# harvester.net
KiCad netlist of a schematic drawn in Altium Designer
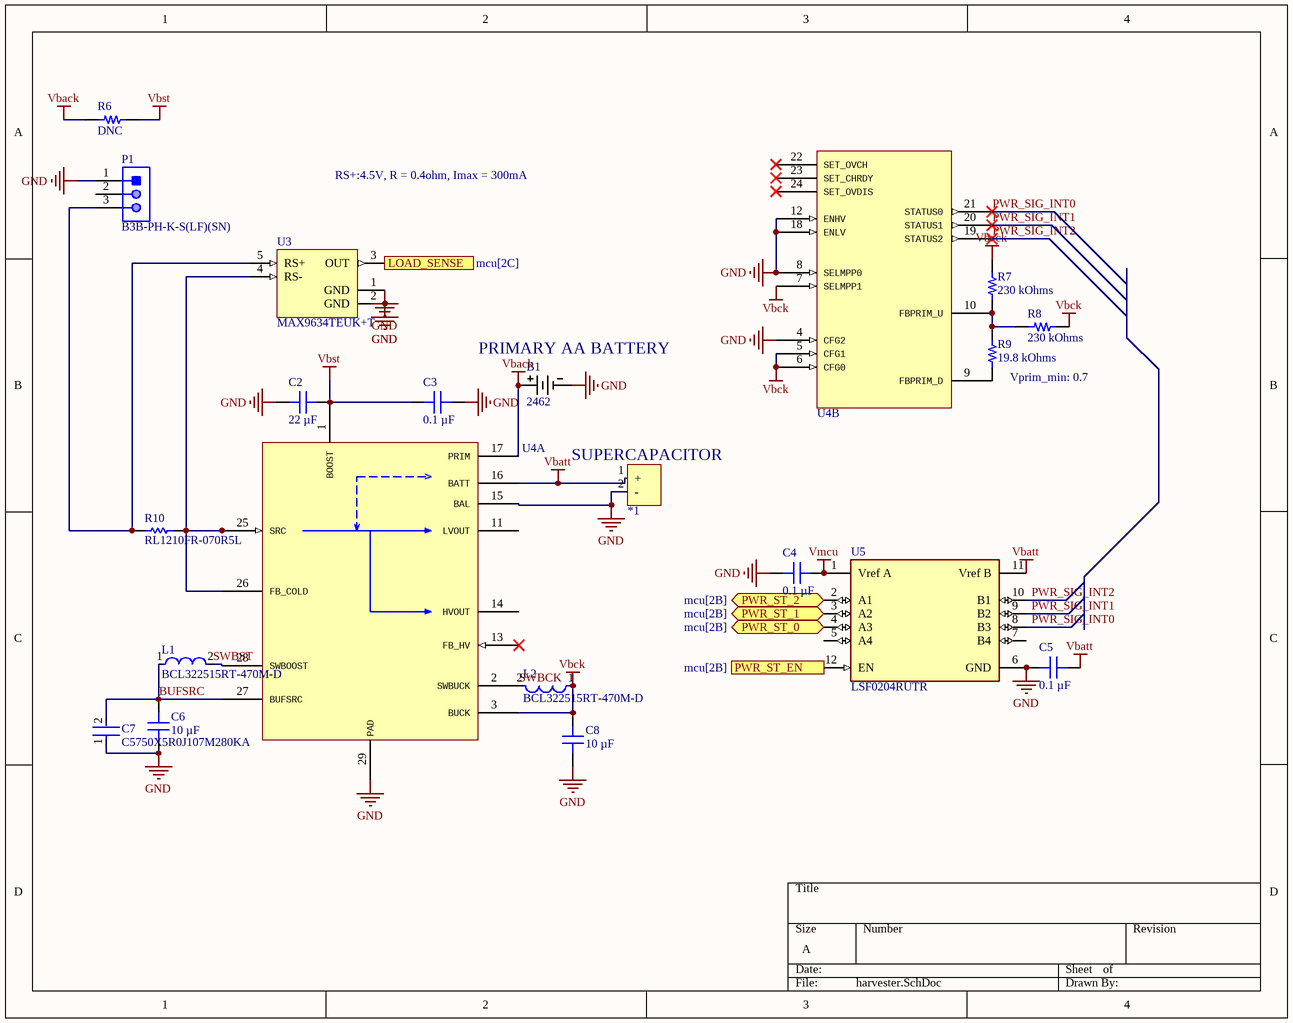
[diagram p0: harvester.SchDoc]

(export (version "E")
  (design (tool "Eeschema 10.0.6"))
  (components
    (comp (ref "*1")
      (value "FC0H474ZFTBR32-SS")
      (footprint "FC0H474ZFTBR32-SS-Footprint-1")
      (description "Cap Supercap 0.47F 5.5V -20% to 80% (16 X 9.5mm) SMD Cylindrical 13 Ohm 70C T/R")
      (libsource (lib "self") (part "FC0H474ZFTBR32-SS"))
    )
    (comp (ref "B1")
      (value "2462")
      (footprint "2462_KEY")
      (description "No Description Available")
      (libsource (lib "2462") (part "2462"))
    )
    (comp (ref "C2")
      (value "22 µF")
      (footprint "CAP 0603_1608")
      (description "CAP CER 22UF 6.3V X5R 0603")
      (fields
        (field (name "PART NUMBER") "GRM188R60J106ME47D")
        (field (name "MANUFACTURER") "Murata Electronics")
      )
      (libsource (lib "Celestial Altium Library - altium_library") (part "Capacitor"))
    )
    (comp (ref "C3")
      (value "0.1 µF")
      (footprint "CAP 0402_1005")
      (description "CAP CER 0.1UF 4V X5R 0402")
      (fields (field (name "PART NUMBER") "C0402C104K7PAC7867") (field (name "MANUFACTURER") "KEMET"))
      (libsource (lib "Celestial Altium Library - altium_library") (part "Capacitor"))
    )
    (comp (ref "C4")
      (value "0.1 µF")
      (footprint "CAP 0402_1005")
      (description "CAP CER 0.1UF 4V X5R 0402")
      (fields (field (name "PART NUMBER") "C0402C104K7PAC7867") (field (name "MANUFACTURER") "KEMET"))
      (libsource (lib "Celestial Altium Library - altium_library") (part "Capacitor"))
    )
    (comp (ref "C5")
      (value "0.1 µF")
      (footprint "CAP 0402_1005")
      (description "CAP CER 0.1UF 4V X5R 0402")
      (fields (field (name "PART NUMBER") "C0402C104K7PAC7867") (field (name "MANUFACTURER") "KEMET"))
      (libsource (lib "Celestial Altium Library - altium_library") (part "Capacitor"))
    )
    (comp (ref "C6")
      (value "10 µF")
      (footprint "CAP 0603_1608")
      (description "CAP CER 10UF 6.3V X5R 0603")
      (fields
        (field (name "PART NUMBER") "GRM188R60J106ME47D")
        (field (name "MANUFACTURER") "Murata Electronics")
      )
      (libsource (lib "Celestial Altium Library - altium_library") (part "Capacitor"))
    )
    (comp (ref "C7")
      (value "C5750X5R0J107M280KA")
      (footprint "FP-C5750-280-0_4-IPC_A")
      (description "Multilayer Ceramic Capacitors 100uF ±20% 6.3V X5R SMD 2220")
      (fields (field (name "TOLERANCE") "20%"))
      (libsource (lib "Altium Content Vault") (part "02cd4be3c70576c341d710602a673aa"))
    )
    (comp (ref "C8")
      (value "10 µF")
      (footprint "CAP 0603_1608")
      (description "CAP CER 10UF 6.3V X5R 0603")
      (fields
        (field (name "PART NUMBER") "GRM188R60J106ME47D")
        (field (name "MANUFACTURER") "Murata Electronics")
      )
      (libsource (lib "Celestial Altium Library - altium_library") (part "Capacitor"))
    )
    (comp (ref "L1")
      (value "BCL322515RT-470M-D")
      (footprint "FP-BCL322515-IPC_C")
      (description "FIXED IND 47UH 670MA 1.4 OHM SMD")
      (libsource (lib "Altium Content Vault") (part "725321dda6339637d4d059423bc1c3c"))
    )
    (comp (ref "L2")
      (value "BCL322515RT-470M-D")
      (footprint "FP-BCL322515-IPC_C")
      (description "FIXED IND 47UH 670MA 1.4 OHM SMD")
      (libsource (lib "Altium Content Vault") (part "725321dda6339637d4d059423bc1c3c"))
    )
    (comp (ref "P1")
      (value "B3B-PH-K-S(LF)(SN)")
      (footprint "JST-B3B-PH-K-S-3_V")
      (fields (field (name "MANUFACTURER") "JST"))
      (libsource (lib "Altium Content Vault") (part "CN-1P-M-R3"))
    )
    (comp (ref "R6")
      (value "DNC")
      (footprint "RES 0402_1005")
      (description "RES 1.5K OHM 0.05% 1/10W 0402")
      (fields
        (field (name "PART NUMBER") "ERA-2VRW1501X")
        (field (name "MANUFACTURER") "Panasonic Electronic Components")
      )
      (libsource (lib "Celestial Altium Library - altium_library") (part "Resistor"))
    )
    (comp (ref "R7")
      (value "230 kOhms")
      (footprint "RES 0402_1005")
      (description "RES 10K OHM 0.1% 1/10W 0402")
      (fields
        (field (name "PART NUMBER") "RP73PF1E10KBTD")
        (field (name "MANUFACTURER") "TE Connectivity Passive Product")
      )
      (libsource (lib "Celestial Altium Library - altium_library") (part "Resistor"))
    )
    (comp (ref "R8")
      (value "230 kOhms")
      (footprint "RES 0402_1005")
      (description "RES 10K OHM 0.1% 1/10W 0402")
      (fields
        (field (name "PART NUMBER") "RP73PF1E10KBTD")
        (field (name "MANUFACTURER") "TE Connectivity Passive Product")
      )
      (libsource (lib "Celestial Altium Library - altium_library") (part "Resistor"))
    )
    (comp (ref "R9")
      (value "19.8 kOhms")
      (footprint "RES 0402_1005")
      (description "RES 10K OHM 0.1% 1/10W 0402")
      (fields
        (field (name "PART NUMBER") "RP73PF1E10KBTD")
        (field (name "MANUFACTURER") "TE Connectivity Passive Product")
      )
      (libsource (lib "Celestial Altium Library - altium_library") (part "Resistor"))
    )
    (comp (ref "R10")
      (value "RL1210FR-070R5L")
      (footprint "RESC3126X65X50NL10T20")
      (fields (field (name "MANUFACTURER") "Yageo"))
      (libsource (lib "Altium Content Vault") (part "RES"))
    )
    (comp (ref "U3")
      (value "MAX9634TEUK+T")
      (footprint "MAXM-U5+2_L")
      (libsource (lib "Altium Content Vault") (part "MAX9XXX-X5XX"))
    )
    (comp (ref "U4")
      (value "AEM10941 - Symbol QFN28")
      (footprint "QFN28 5x5mm Pitch=0.5mm ThPad=3.15x3.15mm")
      (libsource (lib "AEM10941") (part "AEM10941 - Symbol QFN28"))
    )
    (comp (ref "U5")
      (value "LSF0204RUTR")
      (footprint "FP-RUT0012A-MFG")
      (description "IC TRNSLTR BIDIRECTIONAL 12UQFN")
      (libsource (lib "Altium Content Vault") (part "bb5848276c85d13474830c1be14d4a6"))
    )
  )
  (nets
    (net (code "1") (name "/BUFSRC") (class "Default")
      (node (ref "C6") (pin "2") (pinfunction "2_2") (pintype "passive"))
      (node (ref "C7") (pin "2") (pinfunction "2_2") (pintype "passive"))
      (node (ref "L1") (pin "1") (pinfunction "1_1") (pintype "passive"))
      (node (ref "U4") (pin "27") (pinfunction "BUFSRC_27") (pintype "passive"))
    )
    (net (code "2") (name "/LOAD_SENSE") (class "Default")
      (node (ref "U3") (pin "3") (pinfunction "OUT_3") (pintype "output"))
    )
    (net (code "3") (name "/PWR_SIG_INT0") (class "Default")
      (node (ref "U4") (pin "21") (pinfunction "STATUS0_21") (pintype "output"))
      (node (ref "U5") (pin "8") (pinfunction "B3_8") (pintype "bidirectional"))
    )
    (net (code "4") (name "/PWR_SIG_INT1") (class "Default")
      (node (ref "U4") (pin "20") (pinfunction "STATUS1_20") (pintype "output"))
      (node (ref "U5") (pin "9") (pinfunction "B2_9") (pintype "bidirectional"))
    )
    (net (code "5") (name "/PWR_SIG_INT2") (class "Default")
      (node (ref "U4") (pin "19") (pinfunction "STATUS2_19") (pintype "output"))
      (node (ref "U5") (pin "10") (pinfunction "B1_10") (pintype "bidirectional"))
    )
    (net (code "6") (name "/PWR_ST_0") (class "Default")
      (node (ref "U5") (pin "4") (pinfunction "A3_4") (pintype "bidirectional"))
    )
    (net (code "7") (name "/PWR_ST_1") (class "Default")
      (node (ref "U5") (pin "3") (pinfunction "A2_3") (pintype "bidirectional"))
    )
    (net (code "8") (name "/PWR_ST_2") (class "Default")
      (node (ref "U5") (pin "2") (pinfunction "A1_2") (pintype "bidirectional"))
    )
    (net (code "9") (name "/PWR_ST_EN") (class "Default")
      (node (ref "U5") (pin "12") (pinfunction "EN_12") (pintype "input"))
    )
    (net (code "10") (name "/SWBCK") (class "Default")
      (node (ref "L2") (pin "2") (pinfunction "2_2") (pintype "passive"))
      (node (ref "U4") (pin "2") (pinfunction "SWBUCK_2") (pintype "passive"))
    )
    (net (code "11") (name "/SWBST") (class "Default")
      (node (ref "L1") (pin "2") (pinfunction "2_2") (pintype "passive"))
      (node (ref "U4") (pin "28") (pinfunction "SWBOOST_28") (pintype "passive"))
    )
    (net (code "12") (name "GND") (class "Default")
      (node (ref "*1") (pin "2") (pinfunction "-_2") (pintype "power_in"))
      (node (ref "B1") (pin "1") (pinfunction "1_1") (pintype "passive"))
      (node (ref "C2") (pin "1") (pinfunction "1_1") (pintype "passive"))
      (node (ref "C3") (pin "1") (pinfunction "1_1") (pintype "passive"))
      (node (ref "C4") (pin "1") (pinfunction "1_1") (pintype "passive"))
      (node (ref "C5") (pin "2") (pinfunction "2_2") (pintype "passive"))
      (node (ref "C6") (pin "1") (pinfunction "1_1") (pintype "passive"))
      (node (ref "C7") (pin "1") (pinfunction "1_1") (pintype "passive"))
      (node (ref "C8") (pin "2") (pinfunction "2_2") (pintype "passive"))
      (node (ref "P1") (pin "1") (pinfunction "1_1") (pintype "passive"))
      (node (ref "U3") (pin "1") (pinfunction "GND_1") (pintype "power_in"))
      (node (ref "U3") (pin "2") (pinfunction "GND_2") (pintype "power_in"))
      (node (ref "U4") (pin "12") (pinfunction "ENHV_12") (pintype "input"))
      (node (ref "U4") (pin "15") (pinfunction "BAL_15") (pintype "passive"))
      (node (ref "U4") (pin "18") (pinfunction "ENLV_18") (pintype "input"))
      (node (ref "U4") (pin "29") (pinfunction "PAD_29") (pintype "power_in"))
      (node (ref "U4") (pin "4") (pinfunction "CFG2_4") (pintype "input"))
      (node (ref "U4") (pin "8") (pinfunction "SELMPP0_8") (pintype "input"))
      (node (ref "U5") (pin "6") (pinfunction "GND_6") (pintype "power_in"))
    )
    (net (code "13") (name "Net-(U3-RS+)") (class "Default")
      (node (ref "P1") (pin "3") (pinfunction "3_3") (pintype "passive"))
      (node (ref "R10") (pin "1") (pinfunction "1_1") (pintype "passive"))
      (node (ref "U3") (pin "5") (pinfunction "RS+_5") (pintype "input"))
    )
    (net (code "14") (name "Net-(U3-RS-)") (class "Default")
      (node (ref "R10") (pin "2") (pinfunction "2_2") (pintype "passive"))
      (node (ref "U3") (pin "4") (pinfunction "RS-_4") (pintype "input"))
      (node (ref "U4") (pin "25") (pinfunction "SRC_25") (pintype "input"))
      (node (ref "U4") (pin "26") (pinfunction "FB_COLD_26") (pintype "passive"))
    )
    (net (code "15") (name "Net-(U4B-FBPRIM_D)") (class "Default")
      (node (ref "R9") (pin "2") (pinfunction "2_2") (pintype "passive"))
      (node (ref "U4") (pin "9") (pinfunction "FBPRIM_D_9") (pintype "passive"))
    )
    (net (code "16") (name "Net-(U4B-FBPRIM_U)") (class "Default")
      (node (ref "R7") (pin "1") (pinfunction "1_1") (pintype "passive"))
      (node (ref "R8") (pin "1") (pinfunction "1_1") (pintype "passive"))
      (node (ref "R9") (pin "1") (pinfunction "1_1") (pintype "passive"))
      (node (ref "U4") (pin "10") (pinfunction "FBPRIM_U_10") (pintype "passive"))
    )
    (net (code "17") (name "Vback") (class "Default")
      (node (ref "B1") (pin "2") (pinfunction "2_2") (pintype "passive"))
      (node (ref "R6") (pin "2") (pinfunction "2_2") (pintype "passive"))
      (node (ref "R7") (pin "2") (pinfunction "2_2") (pintype "passive"))
      (node (ref "U4") (pin "17") (pinfunction "PRIM_17") (pintype "passive"))
    )
    (net (code "18") (name "Vbatt") (class "Default")
      (node (ref "*1") (pin "1") (pinfunction "+_1") (pintype "power_in"))
      (node (ref "C5") (pin "1") (pinfunction "1_1") (pintype "passive"))
      (node (ref "U4") (pin "16") (pinfunction "BATT_16") (pintype "passive"))
      (node (ref "U5") (pin "11") (pinfunction "Vref_B_11") (pintype "power_in"))
    )
    (net (code "19") (name "Vbck") (class "Default")
      (node (ref "C8") (pin "1") (pinfunction "1_1") (pintype "passive"))
      (node (ref "L2") (pin "1") (pinfunction "1_1") (pintype "passive"))
      (node (ref "R8") (pin "2") (pinfunction "2_2") (pintype "passive"))
      (node (ref "U4") (pin "3") (pinfunction "BUCK_3") (pintype "passive"))
      (node (ref "U4") (pin "5") (pinfunction "CFG1_5") (pintype "input"))
      (node (ref "U4") (pin "6") (pinfunction "CFG0_6") (pintype "input"))
      (node (ref "U4") (pin "7") (pinfunction "SELMPP1_7") (pintype "input"))
    )
    (net (code "20") (name "Vbst") (class "Default")
      (node (ref "C2") (pin "2") (pinfunction "2_2") (pintype "passive"))
      (node (ref "C3") (pin "2") (pinfunction "2_2") (pintype "passive"))
      (node (ref "R6") (pin "1") (pinfunction "1_1") (pintype "passive"))
      (node (ref "U4") (pin "1") (pinfunction "BOOST_1") (pintype "passive"))
    )
    (net (code "21") (name "Vmcu") (class "Default")
      (node (ref "C4") (pin "2") (pinfunction "2_2") (pintype "passive"))
      (node (ref "U5") (pin "1") (pinfunction "Vref_A_1") (pintype "power_in"))
    )
    (net (code "22") (name "unconnected-(P1-Pad2)") (class "Default")
      (node (ref "P1") (pin "2") (pinfunction "2_2") (pintype "passive"))
    )
    (net (code "23") (name "unconnected-(U4A-FB_HV-Pad13)") (class "Default")
      (node (ref "U4") (pin "13") (pinfunction "FB_HV_13") (pintype "input+no_connect"))
    )
    (net (code "24") (name "unconnected-(U4A-HVOUT-Pad14)") (class "Default")
      (node (ref "U4") (pin "14") (pinfunction "HVOUT_14") (pintype "power_in"))
    )
    (net (code "25") (name "unconnected-(U4A-LVOUT-Pad11)") (class "Default")
      (node (ref "U4") (pin "11") (pinfunction "LVOUT_11") (pintype "power_in"))
    )
    (net (code "26") (name "unconnected-(U4B-SET_CHRDY-Pad23)") (class "Default")
      (node (ref "U4") (pin "23") (pinfunction "SET_CHRDY_23") (pintype "passive+no_connect"))
    )
    (net (code "27") (name "unconnected-(U4B-SET_OVCH-Pad22)") (class "Default")
      (node (ref "U4") (pin "22") (pinfunction "SET_OVCH_22") (pintype "passive+no_connect"))
    )
    (net (code "28") (name "unconnected-(U4B-SET_OVDIS-Pad24)") (class "Default")
      (node (ref "U4") (pin "24") (pinfunction "SET_OVDIS_24") (pintype "passive+no_connect"))
    )
    (net (code "29") (name "unconnected-(U5-A4-Pad5)") (class "Default")
      (node (ref "U5") (pin "5") (pinfunction "A4_5") (pintype "bidirectional"))
    )
    (net (code "30") (name "unconnected-(U5-B4-Pad7)") (class "Default")
      (node (ref "U5") (pin "7") (pinfunction "B4_7") (pintype "bidirectional"))
    )
  )
)
